# pic16.net
KiCad netlist of a schematic drawn in EAGLE
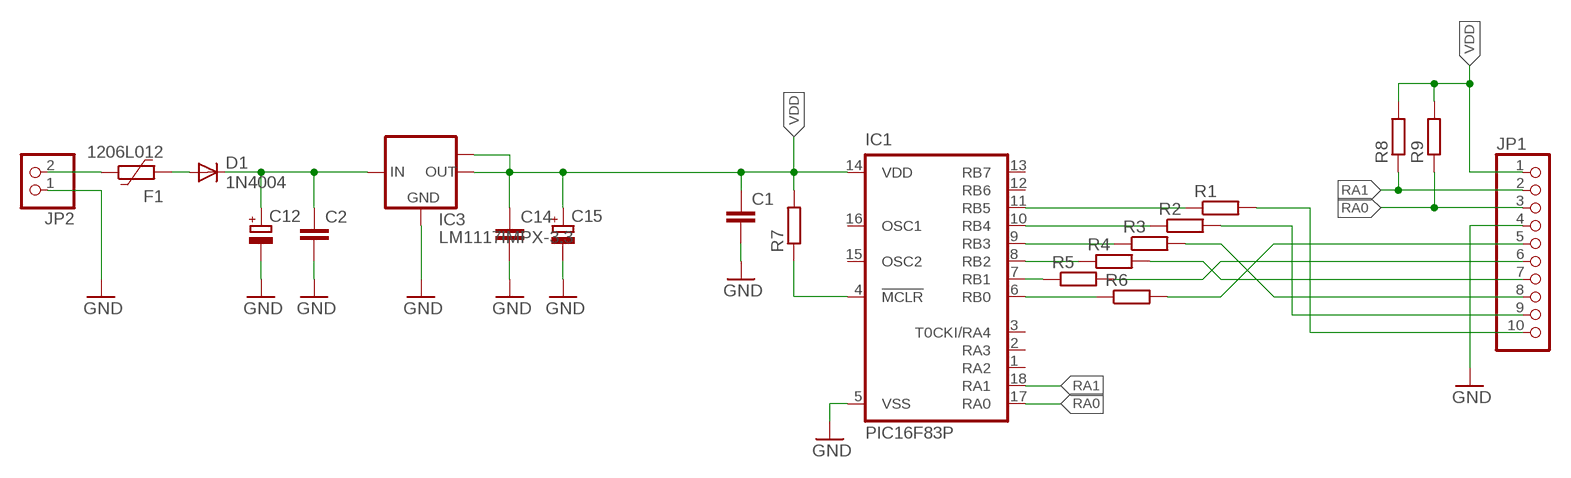
[diagram p0: schematic, sheet 1]

(export (version "E")
  (design (tool "Eeschema 10.0.6"))
  (components
    (comp (ref "C1")
      (value "C-EUC0603")
      (footprint "eagle-import:C0603")
      (libsource (lib "eagle-import") (part "C-EUC0603"))
    )
    (comp (ref "C2")
      (value "C-EUC0603")
      (footprint "eagle-import:C0603")
      (libsource (lib "eagle-import") (part "C-EUC0603"))
    )
    (comp (ref "C12")
      (value "CPOL-EUSMCB")
      (footprint "eagle-import:SMC_B")
      (libsource (lib "eagle-import") (part "CPOL-EUSMCB"))
    )
    (comp (ref "C14")
      (value "C-EUC0603")
      (footprint "eagle-import:C0603")
      (libsource (lib "eagle-import") (part "C-EUC0603"))
    )
    (comp (ref "C15")
      (value "CPOL-EUSMCB")
      (footprint "eagle-import:SMC_B")
      (libsource (lib "eagle-import") (part "CPOL-EUSMCB"))
    )
    (comp (ref "D1")
      (value "1N4004")
      (footprint "eagle-import:DO41-10")
      (libsource (lib "eagle-import") (part "1N4004"))
    )
    (comp (ref "F1")
      (value "1206L012")
      (footprint "eagle-import:1206L")
      (fields (field (name "MF") "Littelfuse"))
      (libsource (lib "eagle-import") (part "?1206L012"))
    )
    (comp (ref "IC1")
      (value "PIC16F83P")
      (footprint "eagle-import:DIL18")
      (fields (field (name "MPN") "PIC16F83-04/P"))
      (libsource (lib "eagle-import") (part "PIC16F8P3"))
    )
    (comp (ref "IC3")
      (value "LM1117IMPX-3.3")
      (footprint "eagle-import:SOT223")
      (libsource (lib "eagle-import") (part "LM1117IMPX-3.3"))
    )
    (comp (ref "JP1")
      (value "PINHD-1X10")
      (footprint "eagle-import:1X10")
      (libsource (lib "eagle-import") (part "PINHD-1X10"))
    )
    (comp (ref "JP2")
      (value "PINHD-1X2")
      (footprint "eagle-import:1X02")
      (libsource (lib "eagle-import") (part "PINHD-1X2"))
    )
    (comp (ref "R1")
      (value "R-EU_R0603")
      (footprint "eagle-import:R0603")
      (libsource (lib "eagle-import") (part "R-EU_R0603"))
    )
    (comp (ref "R2")
      (value "R-EU_R0603")
      (footprint "eagle-import:R0603")
      (libsource (lib "eagle-import") (part "R-EU_R0603"))
    )
    (comp (ref "R3")
      (value "R-EU_R0603")
      (footprint "eagle-import:R0603")
      (libsource (lib "eagle-import") (part "R-EU_R0603"))
    )
    (comp (ref "R4")
      (value "R-EU_R0603")
      (footprint "eagle-import:R0603")
      (libsource (lib "eagle-import") (part "R-EU_R0603"))
    )
    (comp (ref "R5")
      (value "R-EU_R0603")
      (footprint "eagle-import:R0603")
      (libsource (lib "eagle-import") (part "R-EU_R0603"))
    )
    (comp (ref "R6")
      (value "R-EU_R0603")
      (footprint "eagle-import:R0603")
      (libsource (lib "eagle-import") (part "R-EU_R0603"))
    )
    (comp (ref "R7")
      (value "R-EU_R0603")
      (footprint "eagle-import:R0603")
      (libsource (lib "eagle-import") (part "R-EU_R0603"))
    )
    (comp (ref "R8")
      (value "R-EU_0204/5")
      (footprint "eagle-import:0204_5")
      (libsource (lib "eagle-import") (part "R-EU_0204/5"))
    )
    (comp (ref "R9")
      (value "R-EU_0204/5")
      (footprint "eagle-import:0204_5")
      (libsource (lib "eagle-import") (part "R-EU_0204/5"))
    )
  )
  (nets
    (net (code "1") (name "GND") (class "Default")
      (node (ref "C1") (pin "2") (pinfunction "2_2") (pintype "passive"))
      (node (ref "C12") (pin "-") (pinfunction "-_-") (pintype "passive"))
      (node (ref "C14") (pin "2") (pinfunction "2_2") (pintype "passive"))
      (node (ref "C15") (pin "-") (pinfunction "-_-") (pintype "passive"))
      (node (ref "C2") (pin "2") (pinfunction "2_2") (pintype "passive"))
      (node (ref "IC1") (pin "5") (pinfunction "VSS_5") (pintype "power_in"))
      (node (ref "IC3") (pin "1") (pinfunction "GND_1") (pintype "input"))
      (node (ref "JP1") (pin "4") (pinfunction "4_4") (pintype "passive"))
      (node (ref "JP2") (pin "1") (pinfunction "1_1") (pintype "passive"))
    )
    (net (code "2") (name "Net-(D1-PadA)") (class "Default")
      (node (ref "D1") (pin "A") (pinfunction "A_A") (pintype "passive"))
      (node (ref "F1") (pin "2") (pinfunction "2_2") (pintype "passive"))
    )
    (net (code "3") (name "Net-(F1-Pad1)") (class "Default")
      (node (ref "F1") (pin "1") (pinfunction "1_1") (pintype "passive"))
      (node (ref "JP2") (pin "2") (pinfunction "2_2") (pintype "passive"))
    )
    (net (code "4") (name "Net-(IC1-RB0)") (class "Default")
      (node (ref "IC1") (pin "6") (pinfunction "RB0_6") (pintype "bidirectional"))
      (node (ref "R6") (pin "1") (pinfunction "1_1") (pintype "passive"))
    )
    (net (code "5") (name "Net-(IC1-RB1)") (class "Default")
      (node (ref "IC1") (pin "7") (pinfunction "RB1_7") (pintype "bidirectional"))
      (node (ref "R5") (pin "1") (pinfunction "1_1") (pintype "passive"))
    )
    (net (code "6") (name "Net-(IC1-RB2)") (class "Default")
      (node (ref "IC1") (pin "8") (pinfunction "RB2_8") (pintype "bidirectional"))
      (node (ref "R4") (pin "1") (pinfunction "1_1") (pintype "passive"))
    )
    (net (code "7") (name "Net-(IC1-RB3)") (class "Default")
      (node (ref "IC1") (pin "9") (pinfunction "RB3_9") (pintype "bidirectional"))
      (node (ref "R3") (pin "1") (pinfunction "1_1") (pintype "passive"))
    )
    (net (code "8") (name "Net-(IC1-RB4)") (class "Default")
      (node (ref "IC1") (pin "10") (pinfunction "RB4_10") (pintype "bidirectional"))
      (node (ref "R2") (pin "1") (pinfunction "1_1") (pintype "passive"))
    )
    (net (code "9") (name "Net-(IC1-RB5)") (class "Default")
      (node (ref "IC1") (pin "11") (pinfunction "RB5_11") (pintype "bidirectional"))
      (node (ref "R1") (pin "1") (pinfunction "1_1") (pintype "passive"))
    )
    (net (code "10") (name "Net-(IC1-~{MCLR})") (class "Default")
      (node (ref "IC1") (pin "4") (pinfunction "~{MCLR}_4") (pintype "input"))
      (node (ref "R7") (pin "1") (pinfunction "1_1") (pintype "passive"))
    )
    (net (code "11") (name "Net-(IC3-IN)") (class "Default")
      (node (ref "C12") (pin "+") (pinfunction "+_+") (pintype "passive"))
      (node (ref "C2") (pin "1") (pinfunction "1_1") (pintype "passive"))
      (node (ref "D1") (pin "C") (pinfunction "C_C") (pintype "passive"))
      (node (ref "IC3") (pin "3") (pinfunction "IN_3") (pintype "input"))
    )
    (net (code "12") (name "Net-(JP1-Pad5)") (class "Default")
      (node (ref "JP1") (pin "5") (pinfunction "5_5") (pintype "passive"))
      (node (ref "R6") (pin "2") (pinfunction "2_2") (pintype "passive"))
    )
    (net (code "13") (name "Net-(JP1-Pad6)") (class "Default")
      (node (ref "JP1") (pin "6") (pinfunction "6_6") (pintype "passive"))
      (node (ref "R5") (pin "2") (pinfunction "2_2") (pintype "passive"))
    )
    (net (code "14") (name "Net-(JP1-Pad7)") (class "Default")
      (node (ref "JP1") (pin "7") (pinfunction "7_7") (pintype "passive"))
      (node (ref "R4") (pin "2") (pinfunction "2_2") (pintype "passive"))
    )
    (net (code "15") (name "Net-(JP1-Pad8)") (class "Default")
      (node (ref "JP1") (pin "8") (pinfunction "8_8") (pintype "passive"))
      (node (ref "R3") (pin "2") (pinfunction "2_2") (pintype "passive"))
    )
    (net (code "16") (name "Net-(JP1-Pad9)") (class "Default")
      (node (ref "JP1") (pin "9") (pinfunction "9_9") (pintype "passive"))
      (node (ref "R2") (pin "2") (pinfunction "2_2") (pintype "passive"))
    )
    (net (code "17") (name "Net-(JP1-Pad10)") (class "Default")
      (node (ref "JP1") (pin "10") (pinfunction "10_10") (pintype "passive"))
      (node (ref "R1") (pin "2") (pinfunction "2_2") (pintype "passive"))
    )
    (net (code "18") (name "RA0") (class "Default")
      (node (ref "IC1") (pin "17") (pinfunction "RA0_17") (pintype "bidirectional"))
      (node (ref "JP1") (pin "3") (pinfunction "3_3") (pintype "passive"))
      (node (ref "R9") (pin "1") (pinfunction "1_1") (pintype "passive"))
    )
    (net (code "19") (name "RA1") (class "Default")
      (node (ref "IC1") (pin "18") (pinfunction "RA1_18") (pintype "bidirectional"))
      (node (ref "JP1") (pin "2") (pinfunction "2_2") (pintype "passive"))
      (node (ref "R8") (pin "1") (pinfunction "1_1") (pintype "passive"))
    )
    (net (code "20") (name "VDD") (class "Default")
      (node (ref "C1") (pin "1") (pinfunction "1_1") (pintype "passive"))
      (node (ref "C14") (pin "1") (pinfunction "1_1") (pintype "passive"))
      (node (ref "C15") (pin "+") (pinfunction "+_+") (pintype "passive"))
      (node (ref "IC1") (pin "14") (pinfunction "VDD_14") (pintype "power_in"))
      (node (ref "IC3") (pin "2") (pinfunction "OUT_2") (pintype "passive"))
      (node (ref "IC3") (pin "TAB") (pinfunction "OUT1_TAB") (pintype "passive"))
      (node (ref "JP1") (pin "1") (pinfunction "1_1") (pintype "passive"))
      (node (ref "R7") (pin "2") (pinfunction "2_2") (pintype "passive"))
      (node (ref "R8") (pin "2") (pinfunction "2_2") (pintype "passive"))
      (node (ref "R9") (pin "2") (pinfunction "2_2") (pintype "passive"))
    )
    (net (code "21") (name "unconnected-(IC1-OSC1-Pad16)") (class "Default")
      (node (ref "IC1") (pin "16") (pinfunction "OSC1_16") (pintype "input"))
    )
    (net (code "22") (name "unconnected-(IC1-OSC2-Pad15)") (class "Default")
      (node (ref "IC1") (pin "15") (pinfunction "OSC2_15") (pintype "output"))
    )
    (net (code "23") (name "unconnected-(IC1-RA2-Pad1)") (class "Default")
      (node (ref "IC1") (pin "1") (pinfunction "RA2_1") (pintype "bidirectional"))
    )
    (net (code "24") (name "unconnected-(IC1-RA3-Pad2)") (class "Default")
      (node (ref "IC1") (pin "2") (pinfunction "RA3_2") (pintype "bidirectional"))
    )
    (net (code "25") (name "unconnected-(IC1-RB6-Pad12)") (class "Default")
      (node (ref "IC1") (pin "12") (pinfunction "RB6_12") (pintype "bidirectional"))
    )
    (net (code "26") (name "unconnected-(IC1-RB7-Pad13)") (class "Default")
      (node (ref "IC1") (pin "13") (pinfunction "RB7_13") (pintype "bidirectional"))
    )
    (net (code "27") (name "unconnected-(IC1-T0CKI{slash}RA4-Pad3)") (class "Default")
      (node (ref "IC1") (pin "3") (pinfunction "T0CKI/RA4_3") (pintype "bidirectional"))
    )
  )
)
